# Wifiboard.net
KiCad netlist of a schematic drawn in Altium Designer
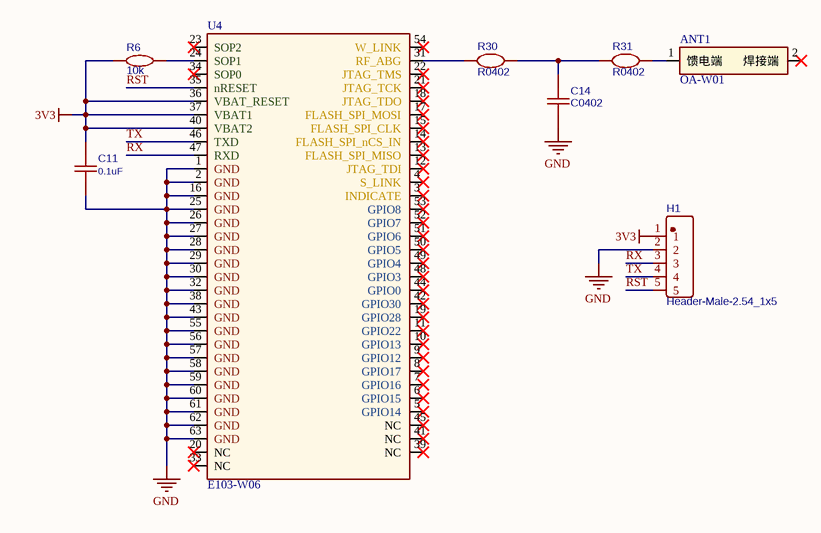
[diagram p0: Wifiboard.SchDoc]

(export (version "E")
  (design (tool "Eeschema 10.0.6"))
  (components
    (comp (ref "ANT1")
      (value "OA-W01")
      (footprint "OA-W01")
      (description "2.4G/5G贴片陶瓷天线")
      (libsource (lib "IC_schlib") (part "OA-W01"))
    )
    (comp (ref "C11")
      (value "0.1uF")
      (footprint "C0603")
      (fields
        (field (name "BOM_MANUFACTURER PART") "CC0603KRX7R9BB104")
        (field (name "BOM_SUPPLIER PART") "C14663")
      )
      (libsource (lib "RC_schlib") (part "C0603"))
    )
    (comp (ref "C14")
      (value "C0402")
      (footprint "C0402")
      (fields
        (field (name "BOM_MANUFACTURER PART") "CC0402KRX7R7BB104")
        (field (name "BOM_SUPPLIER PART") "C60474")
      )
      (libsource (lib "RC_schlib") (part "C0402"))
    )
    (comp (ref "H1")
      (value "Header-Male-2.54_1x5")
      (footprint "HDR2.54-LI-5P")
      (fields (field (name "BOM_SUPPLIER PART") "C247921") (field (name "CONTRIBUTOR") "LCSC"))
      (libsource (lib "2.54CN_schlib") (part "Header-Male-2.54_1x5"))
    )
    (comp (ref "R6")
      (value "10k")
      (footprint "R0603")
      (fields
        (field (name "BOM_SUPPLIER PART") "C326890")
        (field (name "BOM_MANUFACTURER PART") "SR0603JR-071RL")
        (field (name "CONTRIBUTOR") "LCSC")
      )
      (libsource (lib "RC_schlib") (part "R0603"))
    )
    (comp (ref "R30")
      (value "R0402")
      (footprint "R0402")
      (fields
        (field (name "BOM_SUPPLIER PART") "C723595")
        (field (name "BOM_MANUFACTURER PART") "SR0402FR-0710KL")
        (field (name "CONTRIBUTOR") "LCSC")
      )
      (libsource (lib "RC_schlib") (part "R0402"))
    )
    (comp (ref "R31")
      (value "R0402")
      (footprint "R0402")
      (fields
        (field (name "BOM_SUPPLIER PART") "C723595")
        (field (name "BOM_MANUFACTURER PART") "SR0402FR-0710KL")
        (field (name "CONTRIBUTOR") "LCSC")
      )
      (libsource (lib "RC_schlib") (part "R0402"))
    )
    (comp (ref "U4")
      (value "E103-W06")
      (footprint "E103-W06")
      (description "2.4/5Gwifi模块")
      (libsource (lib "W106-W06") (part "E103-W06"))
    )
  )
  (nets
    (net (code "1") (name "/RST") (class "Default")
      (node (ref "H1") (pin "5") (pinfunction "5_5") (pintype "passive"))
      (node (ref "U4") (pin "35") (pinfunction "nRESET_35") (pintype "passive"))
    )
    (net (code "2") (name "/RX") (class "Default")
      (node (ref "H1") (pin "3") (pinfunction "3_3") (pintype "passive"))
      (node (ref "U4") (pin "47") (pinfunction "RXD_47") (pintype "passive"))
    )
    (net (code "3") (name "/TX") (class "Default")
      (node (ref "H1") (pin "4") (pinfunction "4_4") (pintype "passive"))
      (node (ref "U4") (pin "46") (pinfunction "TXD_46") (pintype "passive"))
    )
    (net (code "4") (name "3V3") (class "Default")
      (node (ref "C11") (pin "1") (pinfunction "1_1") (pintype "passive"))
      (node (ref "H1") (pin "1") (pinfunction "1_1") (pintype "passive"))
      (node (ref "R6") (pin "2") (pinfunction "2_2") (pintype "passive"))
      (node (ref "U4") (pin "36") (pinfunction "VBAT_RESET_36") (pintype "passive"))
      (node (ref "U4") (pin "37") (pinfunction "VBAT1_37") (pintype "passive"))
      (node (ref "U4") (pin "40") (pinfunction "VBAT2_40") (pintype "passive"))
    )
    (net (code "5") (name "GND") (class "Default")
      (node (ref "C11") (pin "2") (pinfunction "2_2") (pintype "passive"))
      (node (ref "C14") (pin "1") (pinfunction "1_1") (pintype "passive"))
      (node (ref "H1") (pin "2") (pinfunction "2_2") (pintype "passive"))
      (node (ref "U4") (pin "1") (pinfunction "GND_1") (pintype "passive"))
      (node (ref "U4") (pin "16") (pinfunction "GND_16") (pintype "passive"))
      (node (ref "U4") (pin "2") (pinfunction "GND_2") (pintype "passive"))
      (node (ref "U4") (pin "25") (pinfunction "GND_25") (pintype "passive"))
      (node (ref "U4") (pin "26") (pinfunction "GND_26") (pintype "passive"))
      (node (ref "U4") (pin "27") (pinfunction "GND_27") (pintype "passive"))
      (node (ref "U4") (pin "28") (pinfunction "GND_28") (pintype "passive"))
      (node (ref "U4") (pin "29") (pinfunction "GND_29") (pintype "passive"))
      (node (ref "U4") (pin "30") (pinfunction "GND_30") (pintype "passive"))
      (node (ref "U4") (pin "32") (pinfunction "GND_32") (pintype "passive"))
      (node (ref "U4") (pin "38") (pinfunction "GND_38") (pintype "passive"))
      (node (ref "U4") (pin "43") (pinfunction "GND_43") (pintype "passive"))
      (node (ref "U4") (pin "55") (pinfunction "GND_55") (pintype "passive"))
      (node (ref "U4") (pin "56") (pinfunction "GND_56") (pintype "passive"))
      (node (ref "U4") (pin "57") (pinfunction "GND_57") (pintype "passive"))
      (node (ref "U4") (pin "58") (pinfunction "GND_58") (pintype "passive"))
      (node (ref "U4") (pin "59") (pinfunction "GND_59") (pintype "passive"))
      (node (ref "U4") (pin "60") (pinfunction "GND_60") (pintype "passive"))
      (node (ref "U4") (pin "61") (pinfunction "GND_61") (pintype "passive"))
      (node (ref "U4") (pin "62") (pinfunction "GND_62") (pintype "passive"))
      (node (ref "U4") (pin "63") (pinfunction "GND_63") (pintype "passive"))
    )
    (net (code "6") (name "Net-(ANT1-馈电端)") (class "Default")
      (node (ref "ANT1") (pin "1") (pinfunction "馈电端_1") (pintype "passive"))
      (node (ref "R31") (pin "2") (pinfunction "2_2") (pintype "passive"))
    )
    (net (code "7") (name "Net-(C14-Pad2)") (class "Default")
      (node (ref "C14") (pin "2") (pinfunction "2_2") (pintype "passive"))
      (node (ref "R30") (pin "2") (pinfunction "2_2") (pintype "passive"))
      (node (ref "R31") (pin "1") (pinfunction "1_1") (pintype "passive"))
    )
    (net (code "8") (name "Net-(U4-RF_ABG)") (class "Default")
      (node (ref "R30") (pin "1") (pinfunction "1_1") (pintype "passive"))
      (node (ref "U4") (pin "31") (pinfunction "RF_ABG_31") (pintype "passive"))
    )
    (net (code "9") (name "Net-(U4-SOP1)") (class "Default")
      (node (ref "R6") (pin "1") (pinfunction "1_1") (pintype "passive"))
      (node (ref "U4") (pin "24") (pinfunction "SOP1_24") (pintype "passive"))
    )
    (net (code "10") (name "unconnected-(ANT1-焊接端-Pad2)") (class "Default")
      (node (ref "ANT1") (pin "2") (pinfunction "焊接端_2") (pintype "passive+no_connect"))
    )
    (net (code "11") (name "unconnected-(U4-FLASH_SPI_CLK-Pad15)") (class "Default")
      (node (ref "U4") (pin "15") (pinfunction "FLASH_SPI_CLK_15") (pintype "passive+no_connect"))
    )
    (net (code "12") (name "unconnected-(U4-FLASH_SPI_MISO-Pad13)") (class "Default")
      (node (ref "U4") (pin "13") (pinfunction "FLASH_SPI_MISO_13") (pintype "passive+no_connect"))
    )
    (net (code "13") (name "unconnected-(U4-FLASH_SPI_MOSI-Pad17)") (class "Default")
      (node (ref "U4") (pin "17") (pinfunction "FLASH_SPI_MOSI_17") (pintype "passive+no_connect"))
    )
    (net (code "14") (name "unconnected-(U4-FLASH_SPI_nCS_IN-Pad14)") (class "Default")
      (node (ref "U4") (pin "14") (pinfunction "FLASH_SPI_nCS_IN_14") (pintype "passive+no_connect"))
    )
    (net (code "15") (name "unconnected-(U4-GPIO0-Pad44)") (class "Default")
      (node (ref "U4") (pin "44") (pinfunction "GPIO0_44") (pintype "passive+no_connect"))
    )
    (net (code "16") (name "unconnected-(U4-GPIO3-Pad48)") (class "Default")
      (node (ref "U4") (pin "48") (pinfunction "GPIO3_48") (pintype "passive+no_connect"))
    )
    (net (code "17") (name "unconnected-(U4-GPIO4-Pad49)") (class "Default")
      (node (ref "U4") (pin "49") (pinfunction "GPIO4_49") (pintype "passive+no_connect"))
    )
    (net (code "18") (name "unconnected-(U4-GPIO5-Pad50)") (class "Default")
      (node (ref "U4") (pin "50") (pinfunction "GPIO5_50") (pintype "passive+no_connect"))
    )
    (net (code "19") (name "unconnected-(U4-GPIO6-Pad51)") (class "Default")
      (node (ref "U4") (pin "51") (pinfunction "GPIO6_51") (pintype "passive+no_connect"))
    )
    (net (code "20") (name "unconnected-(U4-GPIO7-Pad52)") (class "Default")
      (node (ref "U4") (pin "52") (pinfunction "GPIO7_52") (pintype "passive+no_connect"))
    )
    (net (code "21") (name "unconnected-(U4-GPIO8-Pad53)") (class "Default")
      (node (ref "U4") (pin "53") (pinfunction "GPIO8_53") (pintype "passive+no_connect"))
    )
    (net (code "22") (name "unconnected-(U4-GPIO12-Pad9)") (class "Default")
      (node (ref "U4") (pin "9") (pinfunction "GPIO12_9") (pintype "passive+no_connect"))
    )
    (net (code "23") (name "unconnected-(U4-GPIO13-Pad10)") (class "Default")
      (node (ref "U4") (pin "10") (pinfunction "GPIO13_10") (pintype "passive+no_connect"))
    )
    (net (code "24") (name "unconnected-(U4-GPIO14-Pad5)") (class "Default")
      (node (ref "U4") (pin "5") (pinfunction "GPIO14_5") (pintype "passive+no_connect"))
    )
    (net (code "25") (name "unconnected-(U4-GPIO15-Pad6)") (class "Default")
      (node (ref "U4") (pin "6") (pinfunction "GPIO15_6") (pintype "passive+no_connect"))
    )
    (net (code "26") (name "unconnected-(U4-GPIO16-Pad7)") (class "Default")
      (node (ref "U4") (pin "7") (pinfunction "GPIO16_7") (pintype "passive+no_connect"))
    )
    (net (code "27") (name "unconnected-(U4-GPIO17-Pad8)") (class "Default")
      (node (ref "U4") (pin "8") (pinfunction "GPIO17_8") (pintype "passive+no_connect"))
    )
    (net (code "28") (name "unconnected-(U4-GPIO22-Pad11)") (class "Default")
      (node (ref "U4") (pin "11") (pinfunction "GPIO22_11") (pintype "passive+no_connect"))
    )
    (net (code "29") (name "unconnected-(U4-GPIO28-Pad19)") (class "Default")
      (node (ref "U4") (pin "19") (pinfunction "GPIO28_19") (pintype "passive+no_connect"))
    )
    (net (code "30") (name "unconnected-(U4-GPIO30-Pad42)") (class "Default")
      (node (ref "U4") (pin "42") (pinfunction "GPIO30_42") (pintype "passive+no_connect"))
    )
    (net (code "31") (name "unconnected-(U4-INDICATE-Pad3)") (class "Default")
      (node (ref "U4") (pin "3") (pinfunction "INDICATE_3") (pintype "passive+no_connect"))
    )
    (net (code "32") (name "unconnected-(U4-JTAG_TCK-Pad21)") (class "Default")
      (node (ref "U4") (pin "21") (pinfunction "JTAG_TCK_21") (pintype "passive+no_connect"))
    )
    (net (code "33") (name "unconnected-(U4-JTAG_TDI-Pad12)") (class "Default")
      (node (ref "U4") (pin "12") (pinfunction "JTAG_TDI_12") (pintype "passive+no_connect"))
    )
    (net (code "34") (name "unconnected-(U4-JTAG_TDO-Pad18)") (class "Default")
      (node (ref "U4") (pin "18") (pinfunction "JTAG_TDO_18") (pintype "passive+no_connect"))
    )
    (net (code "35") (name "unconnected-(U4-JTAG_TMS-Pad22)") (class "Default")
      (node (ref "U4") (pin "22") (pinfunction "JTAG_TMS_22") (pintype "passive+no_connect"))
    )
    (net (code "36") (name "unconnected-(U4-NC-Pad20)") (class "Default")
      (node (ref "U4") (pin "20") (pinfunction "NC_20") (pintype "passive+no_connect"))
    )
    (net (code "37") (name "unconnected-(U4-NC-Pad33)") (class "Default")
      (node (ref "U4") (pin "33") (pinfunction "NC_33") (pintype "passive+no_connect"))
    )
    (net (code "38") (name "unconnected-(U4-NC-Pad39)") (class "Default")
      (node (ref "U4") (pin "39") (pinfunction "NC_39") (pintype "passive+no_connect"))
    )
    (net (code "39") (name "unconnected-(U4-NC-Pad41)") (class "Default")
      (node (ref "U4") (pin "41") (pinfunction "NC_41") (pintype "passive+no_connect"))
    )
    (net (code "40") (name "unconnected-(U4-NC-Pad45)") (class "Default")
      (node (ref "U4") (pin "45") (pinfunction "NC_45") (pintype "passive+no_connect"))
    )
    (net (code "41") (name "unconnected-(U4-SOP0-Pad34)") (class "Default")
      (node (ref "U4") (pin "34") (pinfunction "SOP0_34") (pintype "passive+no_connect"))
    )
    (net (code "42") (name "unconnected-(U4-SOP2-Pad23)") (class "Default")
      (node (ref "U4") (pin "23") (pinfunction "SOP2_23") (pintype "passive+no_connect"))
    )
    (net (code "43") (name "unconnected-(U4-S_LINK-Pad4)") (class "Default")
      (node (ref "U4") (pin "4") (pinfunction "S_LINK_4") (pintype "passive+no_connect"))
    )
    (net (code "44") (name "unconnected-(U4-W_LINK-Pad54)") (class "Default")
      (node (ref "U4") (pin "54") (pinfunction "W_LINK_54") (pintype "passive+no_connect"))
    )
  )
)
